# wheelBoard.net
KiCad netlist of a schematic drawn in EAGLE
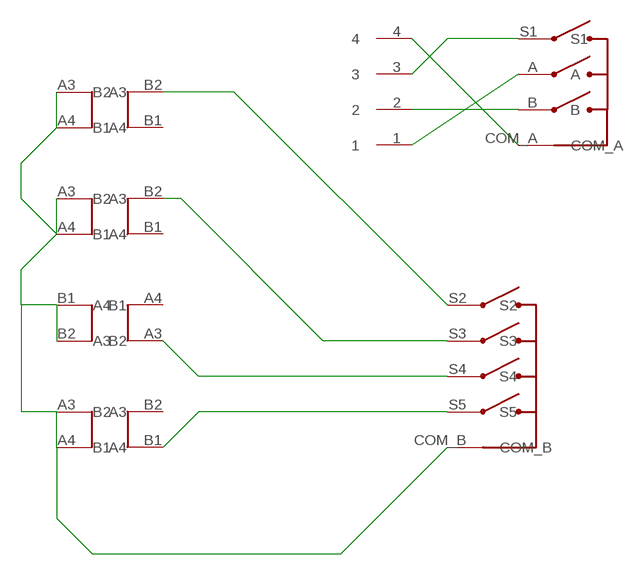
[diagram p0: schematic, sheet 1]

(export (version "E")
  (design (tool "Eeschema 10.0.6"))
  (components
    (comp (ref "U$1")
      (value "TSWB-3N-CB222")
      (footprint "eagle-import:W_DIREC")
      (libsource (lib "eagle-import") (part "TSWB-3N-CB222"))
    )
    (comp (ref "U$2")
      (value "9X_TACT_PATCH")
      (footprint "eagle-import:9XTACTPADS")
      (libsource (lib "eagle-import") (part "9X_TACT_PATCH"))
    )
    (comp (ref "U$3")
      (value "9X_TACT_PATCH")
      (footprint "eagle-import:9XTACTPADS")
      (libsource (lib "eagle-import") (part "9X_TACT_PATCH"))
    )
    (comp (ref "U$4")
      (value "9X_TACT_PATCH")
      (footprint "eagle-import:9XTACTPADS")
      (libsource (lib "eagle-import") (part "9X_TACT_PATCH"))
    )
    (comp (ref "U$5")
      (value "9X_TACT_PATCH")
      (footprint "eagle-import:9XTACTPADS")
      (libsource (lib "eagle-import") (part "9X_TACT_PATCH"))
    )
    (comp (ref "U$6")
      (value "2MM_4P_HEADER")
      (footprint "eagle-import:JST2MM_4P")
      (libsource (lib "eagle-import") (part "2MM_4P_HEADER"))
    )
  )
  (nets
    (net (code "1") (name "Net-(U$1-PadA)") (class "Default")
      (node (ref "U$1") (pin "A") (pinfunction "A_A") (pintype "bidirectional"))
      (node (ref "U$6") (pin "1") (pinfunction "1_1") (pintype "bidirectional"))
    )
    (net (code "2") (name "Net-(U$1-PadB)") (class "Default")
      (node (ref "U$1") (pin "B") (pinfunction "B_B") (pintype "bidirectional"))
      (node (ref "U$6") (pin "2") (pinfunction "2_2") (pintype "bidirectional"))
    )
    (net (code "3") (name "Net-(U$1-PadCOM_A)") (class "Default")
      (node (ref "U$1") (pin "COM_A") (pinfunction "COM_A_COM_A") (pintype "bidirectional"))
      (node (ref "U$6") (pin "4") (pinfunction "4_4") (pintype "bidirectional"))
    )
    (net (code "4") (name "Net-(U$1-PadCOM_B)") (class "Default")
      (node (ref "U$1") (pin "COM_B") (pinfunction "COM_B_COM_B") (pintype "bidirectional"))
      (node (ref "U$2") (pin "A3") (pinfunction "A3_A3") (pintype "bidirectional"))
      (node (ref "U$2") (pin "A4") (pinfunction "A4_A4") (pintype "bidirectional"))
      (node (ref "U$3") (pin "A3") (pinfunction "A3_A3") (pintype "bidirectional"))
      (node (ref "U$3") (pin "A4") (pinfunction "A4_A4") (pintype "bidirectional"))
      (node (ref "U$4") (pin "B1") (pinfunction "B1_B1") (pintype "bidirectional"))
      (node (ref "U$4") (pin "B2") (pinfunction "B2_B2") (pintype "bidirectional"))
      (node (ref "U$5") (pin "A3") (pinfunction "A3_A3") (pintype "bidirectional"))
      (node (ref "U$5") (pin "A4") (pinfunction "A4_A4") (pintype "bidirectional"))
    )
    (net (code "5") (name "Net-(U$1-PadS1)") (class "Default")
      (node (ref "U$1") (pin "S1") (pinfunction "S1_S1") (pintype "bidirectional"))
      (node (ref "U$6") (pin "3") (pinfunction "3_3") (pintype "bidirectional"))
    )
    (net (code "6") (name "Net-(U$1-PadS2)") (class "Default")
      (node (ref "U$1") (pin "S2") (pinfunction "S2_S2") (pintype "bidirectional"))
      (node (ref "U$2") (pin "B2") (pinfunction "B2_B2") (pintype "bidirectional"))
    )
    (net (code "7") (name "Net-(U$1-PadS3)") (class "Default")
      (node (ref "U$1") (pin "S3") (pinfunction "S3_S3") (pintype "bidirectional"))
      (node (ref "U$3") (pin "B2") (pinfunction "B2_B2") (pintype "bidirectional"))
    )
    (net (code "8") (name "Net-(U$1-PadS4)") (class "Default")
      (node (ref "U$1") (pin "S4") (pinfunction "S4_S4") (pintype "bidirectional"))
      (node (ref "U$4") (pin "A3") (pinfunction "A3_A3") (pintype "bidirectional"))
    )
    (net (code "9") (name "Net-(U$1-PadS5)") (class "Default")
      (node (ref "U$1") (pin "S5") (pinfunction "S5_S5") (pintype "bidirectional"))
      (node (ref "U$5") (pin "B1") (pinfunction "B1_B1") (pintype "bidirectional"))
    )
    (net (code "10") (name "unconnected-(U$2-PadB1)") (class "Default")
      (node (ref "U$2") (pin "B1") (pinfunction "B1_B1") (pintype "bidirectional"))
    )
    (net (code "11") (name "unconnected-(U$3-PadB1)") (class "Default")
      (node (ref "U$3") (pin "B1") (pinfunction "B1_B1") (pintype "bidirectional"))
    )
    (net (code "12") (name "unconnected-(U$4-PadA4)") (class "Default")
      (node (ref "U$4") (pin "A4") (pinfunction "A4_A4") (pintype "bidirectional"))
    )
    (net (code "13") (name "unconnected-(U$5-PadB2)") (class "Default")
      (node (ref "U$5") (pin "B2") (pinfunction "B2_B2") (pintype "bidirectional"))
    )
  )
)
